# FastDAC.net
KiCad netlist of a schematic drawn in Altium Designer
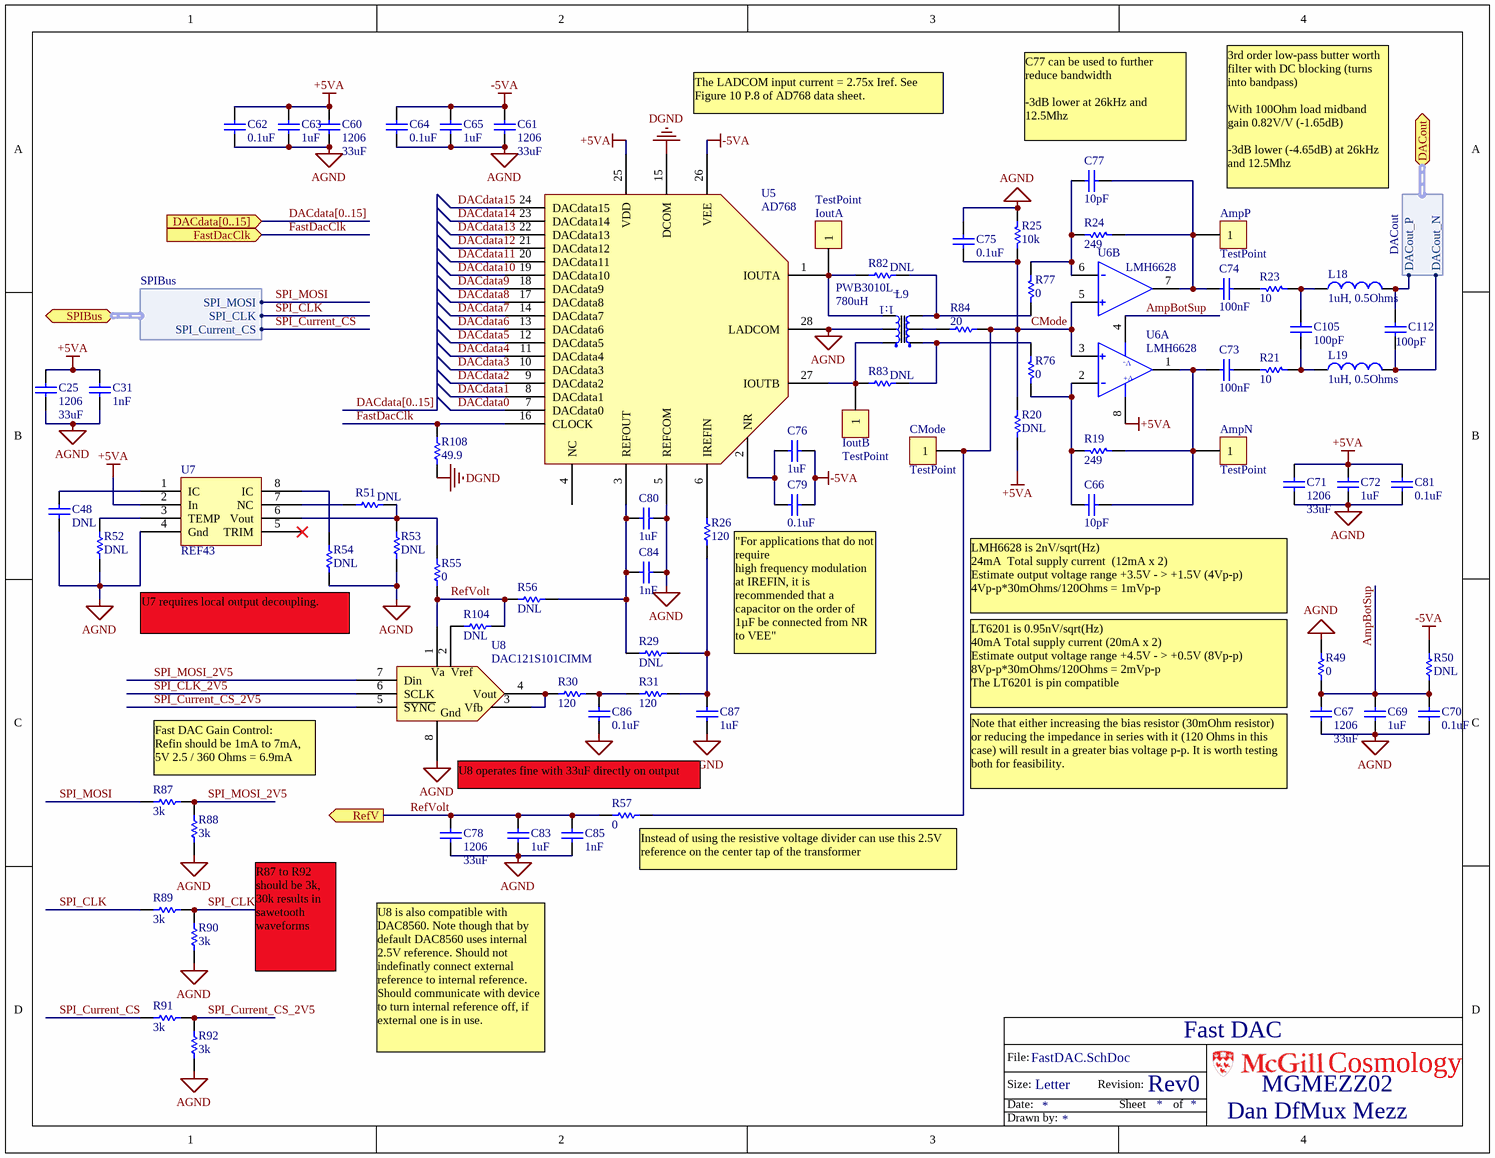
[diagram p0: FastDAC.SchDoc]

(export (version "E")
  (design (tool "Eeschema 10.0.6"))
  (components
    (comp (ref "AmpN")
      (value "TestPoint")
      (footprint "TP-3520-SK")
      (description "TestPoint1")
      (libsource (lib "") (part "TestPoint_3"))
    )
    (comp (ref "AmpP")
      (value "TestPoint")
      (footprint "TP-3520-SK")
      (description "TestPoint1")
      (libsource (lib "") (part "TestPoint_3"))
    )
    (comp (ref "C25")
      (value "33uF")
      (footprint "1206")
      (description "Capacitor, Ceramic, 1210")
      (fields
        (field (name "MANUFACTURER") "TDK Corporation")
        (field (name "MANUFACTURERS PART NUMBER") "C3216X5R1E336M")
      )
      (libsource (lib "MGMEZZ04") (part "CAP 1210"))
    )
    (comp (ref "C31")
      (value "1nF")
      (footprint "0603")
      (description "Capacitor, Ceramic, 0603")
      (fields (field (name "MANUFACTURER") "Generic"))
      (libsource (lib "MGMEZZ04") (part "CAP 0603"))
    )
    (comp (ref "C48")
      (value "DNL")
      (footprint "0603")
      (description "Capacitor, Ceramic, 0603")
      (fields (field (name "MANUFACTURER") "Generic"))
      (libsource (lib "MGMEZZ04") (part "CAP 0603"))
    )
    (comp (ref "C60")
      (value "33uF")
      (footprint "1206")
      (description "Capacitor, Ceramic, 1210")
      (fields
        (field (name "MANUFACTURER") "TDK Corporation")
        (field (name "MANUFACTURERS PART NUMBER") "C3216X5R1E336M")
      )
      (libsource (lib "MGMEZZ04") (part "CAP 1210"))
    )
    (comp (ref "C61")
      (value "33uF")
      (footprint "1206")
      (description "Capacitor, Ceramic, 1210")
      (fields
        (field (name "MANUFACTURER") "TDK Corporation")
        (field (name "MANUFACTURERS PART NUMBER") "C3216X5R1E336M")
      )
      (libsource (lib "MGMEZZ04") (part "CAP 1210"))
    )
    (comp (ref "C62")
      (value "0.1uF")
      (footprint "0603")
      (description "Capacitor, Ceramic, 0603")
      (fields (field (name "MANUFACTURER") "Generic"))
      (libsource (lib "MGMEZZ04") (part "CAP 0603"))
    )
    (comp (ref "C63")
      (value "1uF")
      (footprint "0603")
      (description "Capacitor, Ceramic, 0603")
      (fields
        (field (name "MANUFACTURER") "Generic")
        (field (name "MANUFACTURERS PART NUMBER") "e.g C1608X7R1C105K")
      )
      (libsource (lib "MGMEZZ04") (part "CAP 0603"))
    )
    (comp (ref "C64")
      (value "0.1uF")
      (footprint "0603")
      (description "Capacitor, Ceramic, 0603")
      (fields (field (name "MANUFACTURER") "Generic"))
      (libsource (lib "MGMEZZ04") (part "CAP 0603"))
    )
    (comp (ref "C65")
      (value "1uF")
      (footprint "0603")
      (description "Capacitor, Ceramic, 0603")
      (fields
        (field (name "MANUFACTURER") "Generic")
        (field (name "MANUFACTURERS PART NUMBER") "e.g C1608X7R1C105K")
      )
      (libsource (lib "MGMEZZ04") (part "CAP 0603"))
    )
    (comp (ref "C66")
      (value "10pF")
      (footprint "0603")
      (description "Capacitor, Ceramic, 0603")
      (fields (field (name "MANUFACTURER") "Generic"))
      (libsource (lib "MGMEZZ04") (part "CAP 0603"))
    )
    (comp (ref "C67")
      (value "33uF")
      (footprint "1206")
      (description "Capacitor, Ceramic, 1210")
      (fields
        (field (name "MANUFACTURER") "TDK Corporation")
        (field (name "MANUFACTURERS PART NUMBER") "C3216X5R1E336M")
      )
      (libsource (lib "MGMEZZ04") (part "CAP 1210"))
    )
    (comp (ref "C69")
      (value "1uF")
      (footprint "0603")
      (description "Capacitor, Ceramic, 0603")
      (fields
        (field (name "MANUFACTURER") "Generic")
        (field (name "MANUFACTURERS PART NUMBER") "e.g C1608X7R1C105K")
      )
      (libsource (lib "MGMEZZ04") (part "CAP 0603"))
    )
    (comp (ref "C70")
      (value "0.1uF")
      (footprint "0603")
      (description "Capacitor, Ceramic, 0603")
      (fields (field (name "MANUFACTURER") "Generic"))
      (libsource (lib "MGMEZZ04") (part "CAP 0603"))
    )
    (comp (ref "C71")
      (value "33uF")
      (footprint "1206")
      (description "Capacitor, Ceramic, 1210")
      (fields
        (field (name "MANUFACTURER") "TDK Corporation")
        (field (name "MANUFACTURERS PART NUMBER") "C3216X5R1E336M")
      )
      (libsource (lib "MGMEZZ04") (part "CAP 1210"))
    )
    (comp (ref "C72")
      (value "1uF")
      (footprint "0603")
      (description "Capacitor, Ceramic, 0603")
      (fields
        (field (name "MANUFACTURER") "Generic")
        (field (name "MANUFACTURERS PART NUMBER") "e.g C1608X7R1C105K")
      )
      (libsource (lib "MGMEZZ04") (part "CAP 0603"))
    )
    (comp (ref "C73")
      (value "100nF")
      (footprint "0603")
      (description "Capacitor, Ceramic, 0603")
      (fields (field (name "MANUFACTURER") "Generic"))
      (libsource (lib "MGMEZZ04") (part "CAP 0603"))
    )
    (comp (ref "C74")
      (value "100nF")
      (footprint "0603")
      (description "Capacitor, Ceramic, 0603")
      (fields (field (name "MANUFACTURER") "Generic"))
      (libsource (lib "MGMEZZ04") (part "CAP 0603"))
    )
    (comp (ref "C75")
      (value "0.1uF")
      (footprint "0603")
      (description "Capacitor, Ceramic, 0603")
      (fields (field (name "MANUFACTURER") "Generic"))
      (libsource (lib "MGMEZZ04") (part "CAP 0603"))
    )
    (comp (ref "C76")
      (value "1uF")
      (footprint "0603")
      (description "Capacitor, Ceramic, 0603")
      (fields
        (field (name "MANUFACTURER") "Generic")
        (field (name "MANUFACTURERS PART NUMBER") "e.g C1608X7R1C105K")
      )
      (libsource (lib "MGMEZZ04") (part "CAP 0603"))
    )
    (comp (ref "C77")
      (value "10pF")
      (footprint "0603")
      (description "Capacitor, Ceramic, 0603")
      (fields (field (name "MANUFACTURER") "Generic"))
      (libsource (lib "MGMEZZ04") (part "CAP 0603"))
    )
    (comp (ref "C78")
      (value "33uF")
      (footprint "1206")
      (description "Capacitor, Ceramic, 1210")
      (fields
        (field (name "MANUFACTURER") "TDK Corporation")
        (field (name "MANUFACTURERS PART NUMBER") "C3216X5R1E336M")
      )
      (libsource (lib "MGMEZZ04") (part "CAP 1210"))
    )
    (comp (ref "C79")
      (value "0.1uF")
      (footprint "0603")
      (description "Capacitor, Ceramic, 0603")
      (fields (field (name "MANUFACTURER") "Generic"))
      (libsource (lib "MGMEZZ04") (part "CAP 0603"))
    )
    (comp (ref "C80")
      (value "1uF")
      (footprint "0603")
      (description "Capacitor, Ceramic, 0603")
      (fields
        (field (name "MANUFACTURER") "Generic")
        (field (name "MANUFACTURERS PART NUMBER") "e.g C1608X7R1C105K")
      )
      (libsource (lib "MGMEZZ04") (part "CAP 0603"))
    )
    (comp (ref "C81")
      (value "0.1uF")
      (footprint "0603")
      (description "Capacitor, Ceramic, 0603")
      (fields (field (name "MANUFACTURER") "Generic"))
      (libsource (lib "MGMEZZ04") (part "CAP 0603"))
    )
    (comp (ref "C83")
      (value "1uF")
      (footprint "0603")
      (description "Capacitor, Ceramic, 0603")
      (fields
        (field (name "MANUFACTURER") "Generic")
        (field (name "MANUFACTURERS PART NUMBER") "e.g C1608X7R1C105K")
      )
      (libsource (lib "MGMEZZ04") (part "CAP 0603"))
    )
    (comp (ref "C84")
      (value "1nF")
      (footprint "0603")
      (description "Capacitor, Ceramic, 0603")
      (fields (field (name "MANUFACTURER") "Generic"))
      (libsource (lib "MGMEZZ04") (part "CAP 0603"))
    )
    (comp (ref "C85")
      (value "1nF")
      (footprint "0603")
      (description "Capacitor, Ceramic, 0603")
      (fields (field (name "MANUFACTURER") "Generic"))
      (libsource (lib "MGMEZZ04") (part "CAP 0603"))
    )
    (comp (ref "C86")
      (value "0.1uF")
      (footprint "0603")
      (description "Capacitor, Ceramic, 0603")
      (fields (field (name "MANUFACTURER") "Generic"))
      (libsource (lib "MGMEZZ04") (part "CAP 0603"))
    )
    (comp (ref "C87")
      (value "1uF")
      (footprint "0603")
      (description "Capacitor, Ceramic, 0603")
      (fields
        (field (name "MANUFACTURER") "Generic")
        (field (name "MANUFACTURERS PART NUMBER") "e.g C1608X7R1C105K")
      )
      (libsource (lib "MGMEZZ04") (part "CAP 0603"))
    )
    (comp (ref "C105")
      (value "100pF")
      (footprint "0603")
      (description "Capacitor, Ceramic, 0603")
      (fields (field (name "MANUFACTURER") "Generic"))
      (libsource (lib "MGMEZZ04") (part "CAP 0603"))
    )
    (comp (ref "C112")
      (value "100pF")
      (footprint "0603")
      (description "Capacitor, Ceramic, 0603")
      (fields (field (name "MANUFACTURER") "Generic"))
      (libsource (lib "MGMEZZ04") (part "CAP 0603"))
    )
    (comp (ref "CMode")
      (value "TestPoint")
      (footprint "TP-3520-SK")
      (description "TestPoint1")
      (libsource (lib "MGMEZZ04") (part "TestPoint"))
    )
    (comp (ref "IoutA")
      (value "TestPoint")
      (footprint "TP-3520-SK")
      (description "TestPoint1")
      (libsource (lib "") (part "TestPoint_1"))
    )
    (comp (ref "IoutB")
      (value "TestPoint")
      (footprint "TP-3520-SK")
      (description "TestPoint1")
      (libsource (lib "") (part "TestPoint_2"))
    )
    (comp (ref "L9")
      (value "PWB3010L_")
      (footprint "PWB")
      (description "Transformer")
      (fields (field (name "MANUFACTURER") "Coil Craft") (field (name "ALTIUM_VALUE") "780uH"))
      (libsource (lib "MGMEZZ04") (part "PWB-1-CLB"))
    )
    (comp (ref "L18")
      (value "1uH, 0.5Ohms")
      (footprint "0805")
      (description "Inductor 0805")
      (fields
        (field (name "MANUFACTURER") "EPCOS Inc")
        (field (name "MANUFACTURERS PART NUMBER") "B82498F1102J")
      )
      (libsource (lib "MGMEZZ04") (part "IND 0805"))
    )
    (comp (ref "L19")
      (value "1uH, 0.5Ohms")
      (footprint "0805")
      (description "Inductor 0805")
      (fields
        (field (name "MANUFACTURER") "EPCOS Inc")
        (field (name "MANUFACTURERS PART NUMBER") "B82498F1102J")
      )
      (libsource (lib "MGMEZZ04") (part "IND 0805"))
    )
    (comp (ref "R19")
      (value "249")
      (footprint "0603")
      (description "Resistor")
      (fields (field (name "MANUFACTURER") "Generic"))
      (libsource (lib "MGMEZZ04") (part "RES 0603"))
    )
    (comp (ref "R20")
      (value "DNL")
      (footprint "0603")
      (description "Resistor")
      (fields (field (name "MANUFACTURER") "Generic"))
      (libsource (lib "MGMEZZ04") (part "RES 0603"))
    )
    (comp (ref "R21")
      (value "10")
      (footprint "0603")
      (description "Resistor")
      (fields (field (name "MANUFACTURER") "Generic"))
      (libsource (lib "MGMEZZ04") (part "RES 0603"))
    )
    (comp (ref "R23")
      (value "10")
      (footprint "0603")
      (description "Resistor")
      (fields (field (name "MANUFACTURER") "Generic"))
      (libsource (lib "MGMEZZ04") (part "RES 0603"))
    )
    (comp (ref "R24")
      (value "249")
      (footprint "0603")
      (description "Resistor")
      (fields (field (name "MANUFACTURER") "Generic"))
      (libsource (lib "MGMEZZ04") (part "RES 0603"))
    )
    (comp (ref "R25")
      (value "10k")
      (footprint "0603")
      (description "Resistor")
      (fields (field (name "MANUFACTURER") "Generic"))
      (libsource (lib "MGMEZZ04") (part "RES 0603"))
    )
    (comp (ref "R26")
      (value "120")
      (footprint "0603")
      (description "Resistor")
      (fields (field (name "MANUFACTURER") "Generic"))
      (libsource (lib "MGMEZZ04") (part "RES 0603"))
    )
    (comp (ref "R29")
      (value "DNL")
      (footprint "0603")
      (description "Resistor")
      (fields (field (name "MANUFACTURER") "Generic"))
      (libsource (lib "MGMEZZ04") (part "RES 0603"))
    )
    (comp (ref "R30")
      (value "120")
      (footprint "0603")
      (description "Resistor")
      (fields (field (name "MANUFACTURER") "Generic"))
      (libsource (lib "MGMEZZ04") (part "RES 0603"))
    )
    (comp (ref "R31")
      (value "120")
      (footprint "0603")
      (description "Resistor")
      (fields (field (name "MANUFACTURER") "Generic"))
      (libsource (lib "MGMEZZ04") (part "RES 0603"))
    )
    (comp (ref "R49")
      (value "0")
      (footprint "0603")
      (description "Resistor")
      (fields (field (name "MANUFACTURER") "Generic"))
      (libsource (lib "MGMEZZ04") (part "RES 0603"))
    )
    (comp (ref "R50")
      (value "DNL")
      (footprint "0603")
      (description "Resistor")
      (fields (field (name "MANUFACTURER") "Generic"))
      (libsource (lib "MGMEZZ04") (part "RES 0603"))
    )
    (comp (ref "R51")
      (value "DNL")
      (footprint "0603")
      (description "Resistor")
      (fields (field (name "MANUFACTURER") "Generic"))
      (libsource (lib "MGMEZZ04") (part "RES 0603"))
    )
    (comp (ref "R52")
      (value "DNL")
      (footprint "0603")
      (description "Resistor")
      (fields (field (name "MANUFACTURER") "Generic"))
      (libsource (lib "MGMEZZ04") (part "RES 0603"))
    )
    (comp (ref "R53")
      (value "DNL")
      (footprint "0603")
      (description "Resistor")
      (fields (field (name "MANUFACTURER") "Generic"))
      (libsource (lib "MGMEZZ04") (part "RES 0603"))
    )
    (comp (ref "R54")
      (value "DNL")
      (footprint "0603")
      (description "Resistor")
      (fields (field (name "MANUFACTURER") "Generic"))
      (libsource (lib "MGMEZZ04") (part "RES 0603"))
    )
    (comp (ref "R55")
      (value "0")
      (footprint "0603")
      (description "Resistor")
      (fields (field (name "MANUFACTURER") "Generic"))
      (libsource (lib "MGMEZZ04") (part "RES 0603"))
    )
    (comp (ref "R56")
      (value "DNL")
      (footprint "0603")
      (description "Resistor")
      (fields (field (name "MANUFACTURER") "Generic"))
      (libsource (lib "MGMEZZ04") (part "RES 0603"))
    )
    (comp (ref "R57")
      (value "0")
      (footprint "0603")
      (description "Resistor")
      (fields (field (name "MANUFACTURER") "Generic"))
      (libsource (lib "MGMEZZ04") (part "RES 0603"))
    )
    (comp (ref "R76")
      (value "0")
      (footprint "0603")
      (description "Resistor")
      (fields (field (name "MANUFACTURER") "Generic"))
      (libsource (lib "MGMEZZ04") (part "RES 0603"))
    )
    (comp (ref "R77")
      (value "0")
      (footprint "0603")
      (description "Resistor")
      (fields (field (name "MANUFACTURER") "Generic"))
      (libsource (lib "MGMEZZ04") (part "RES 0603"))
    )
    (comp (ref "R82")
      (value "DNL")
      (footprint "0603")
      (description "Resistor")
      (fields (field (name "MANUFACTURER") "Generic"))
      (libsource (lib "MGMEZZ04") (part "RES 0603"))
    )
    (comp (ref "R83")
      (value "DNL")
      (footprint "0603")
      (description "Resistor")
      (fields (field (name "MANUFACTURER") "Generic"))
      (libsource (lib "MGMEZZ04") (part "RES 0603"))
    )
    (comp (ref "R84")
      (value "20")
      (footprint "0603")
      (description "Resistor")
      (fields (field (name "MANUFACTURER") "Generic"))
      (libsource (lib "MGMEZZ04") (part "RES 0603"))
    )
    (comp (ref "R87")
      (value "3k")
      (footprint "0603")
      (description "Resistor")
      (fields (field (name "MANUFACTURER") "Generic"))
      (libsource (lib "MGMEZZ04") (part "RES 0603"))
    )
    (comp (ref "R88")
      (value "3k")
      (footprint "0603")
      (description "Resistor")
      (fields (field (name "MANUFACTURER") "Generic"))
      (libsource (lib "MGMEZZ04") (part "RES 0603"))
    )
    (comp (ref "R89")
      (value "3k")
      (footprint "0603")
      (description "Resistor")
      (fields (field (name "MANUFACTURER") "Generic"))
      (libsource (lib "MGMEZZ04") (part "RES 0603"))
    )
    (comp (ref "R90")
      (value "3k")
      (footprint "0603")
      (description "Resistor")
      (fields (field (name "MANUFACTURER") "Generic"))
      (libsource (lib "MGMEZZ04") (part "RES 0603"))
    )
    (comp (ref "R91")
      (value "3k")
      (footprint "0603")
      (description "Resistor")
      (fields (field (name "MANUFACTURER") "Generic"))
      (libsource (lib "MGMEZZ04") (part "RES 0603"))
    )
    (comp (ref "R92")
      (value "3k")
      (footprint "0603")
      (description "Resistor")
      (fields (field (name "MANUFACTURER") "Generic"))
      (libsource (lib "MGMEZZ04") (part "RES 0603"))
    )
    (comp (ref "R104")
      (value "DNL")
      (footprint "0603")
      (description "Resistor")
      (fields (field (name "MANUFACTURER") "Generic"))
      (libsource (lib "MGMEZZ04") (part "RES 0603"))
    )
    (comp (ref "R108")
      (value "49.9")
      (footprint "0603")
      (description "Resistor")
      (fields (field (name "MANUFACTURER") "Generic"))
      (libsource (lib "MGMEZZ04") (part "RES 0603"))
    )
    (comp (ref "U5")
      (value "AD768")
      (footprint "SOIC 28 300mils")
      (description "DAC 16bit 30MSPS")
      (fields
        (field (name "MANUFACTURERS PART NUMBER") "AD768ARZ")
        (field (name "MANUFACTURER") "Analog Devices")
      )
      (libsource (lib "MGMEZZ04") (part "AD768"))
    )
    (comp (ref "U6")
      (value "LMH6628")
      (footprint "SO8")
      (description "Dual Opamp 200Mhz GBP Soic 8")
      (fields
        (field (name "MANUFACTURERS PART NUMBER") "LMH6628MA/NOPB")
        (field (name "MANUFACTURER") "National Semiconductor")
      )
      (libsource (lib "MGMEZZ04") (part "LMH6628"))
    )
    (comp (ref "U7")
      (value "REF43")
      (footprint "SO8")
      (description "Voltage Referance")
      (fields
        (field (name "MANUFACTURER") "Analog Devices")
        (field (name "MANUFACTURERS PART NUMBER") "REF43GSZ")
      )
      (libsource (lib "MGMEZZ04") (part "REF43"))
    )
    (comp (ref "U8")
      (value "DAC121S101CIMM")
      (footprint "MSOP-8")
      (description "CONV D/A 12BIT MICROPWR 8MSOP")
      (fields
        (field (name "MANUFACTURER") "National Semiconductor")
        (field (name "MANUFACTURERS PART NUMBER") "DAC121S101CIMM/NOPB")
      )
      (libsource (lib "MGMEZZ04") (part "DAC121S101CIMM/NOPB"))
    )
  )
  (nets
    (net (code "3") (name "+5VA") (class "Default")
      (node (ref "C25") (pin "1") (pinfunction "1_1") (pintype "passive"))
      (node (ref "C31") (pin "1") (pinfunction "1_1") (pintype "passive"))
      (node (ref "C60") (pin "2") (pinfunction "2_2") (pintype "passive"))
      (node (ref "C62") (pin "2") (pinfunction "2_2") (pintype "passive"))
      (node (ref "C63") (pin "2") (pinfunction "2_2") (pintype "passive"))
      (node (ref "C71") (pin "2") (pinfunction "2_2") (pintype "passive"))
      (node (ref "C72") (pin "1") (pinfunction "1_1") (pintype "passive"))
      (node (ref "C81") (pin "1") (pinfunction "1_1") (pintype "passive"))
      (node (ref "R20") (pin "2") (pinfunction "2_2") (pintype "passive"))
      (node (ref "U5") (pin "25") (pinfunction "VDD_25") (pintype "passive"))
      (node (ref "U6") (pin "8") (pinfunction "V+_8") (pintype "power_in"))
      (node (ref "U7") (pin "2") (pinfunction "In_2") (pintype "passive"))
    )
    (net (code "4") (name "-5VA") (class "Default")
      (node (ref "C61") (pin "2") (pinfunction "2_2") (pintype "passive"))
      (node (ref "C64") (pin "2") (pinfunction "2_2") (pintype "passive"))
      (node (ref "C65") (pin "2") (pinfunction "2_2") (pintype "passive"))
      (node (ref "C76") (pin "1") (pinfunction "1_1") (pintype "passive"))
      (node (ref "C79") (pin "1") (pinfunction "1_1") (pintype "passive"))
      (node (ref "R50") (pin "2") (pinfunction "2_2") (pintype "passive"))
      (node (ref "U5") (pin "26") (pinfunction "VEE_26") (pintype "passive"))
    )
    (net (code "5") (name "/AmpBotSup") (class "Default")
      (node (ref "C67") (pin "2") (pinfunction "2_2") (pintype "passive"))
      (node (ref "C69") (pin "1") (pinfunction "1_1") (pintype "passive"))
      (node (ref "C70") (pin "1") (pinfunction "1_1") (pintype "passive"))
      (node (ref "R49") (pin "1") (pinfunction "1_1") (pintype "passive"))
      (node (ref "R50") (pin "1") (pinfunction "1_1") (pintype "passive"))
      (node (ref "U6") (pin "4") (pinfunction "V-_4") (pintype "power_in"))
    )
    (net (code "6") (name "/CMode") (class "Default")
      (node (ref "C75") (pin "2") (pinfunction "2_2") (pintype "passive"))
      (node (ref "CMode") (pin "1") (pinfunction "1_1") (pintype "passive"))
      (node (ref "R20") (pin "1") (pinfunction "1_1") (pintype "passive"))
      (node (ref "R25") (pin "2") (pinfunction "2_2") (pintype "passive"))
      (node (ref "R57") (pin "2") (pinfunction "2_2") (pintype "passive"))
      (node (ref "R84") (pin "2") (pinfunction "2_2") (pintype "passive"))
      (node (ref "U6") (pin "3") (pinfunction "IN+_3") (pintype "passive"))
      (node (ref "U6") (pin "5") (pinfunction "IN+_5") (pintype "passive"))
    )
    (net (code "7") (name "/DACdata0") (class "Default")
      (node (ref "U5") (pin "7") (pinfunction "DACdata0_7") (pintype "passive"))
    )
    (net (code "8") (name "/DACdata1") (class "Default")
      (node (ref "U5") (pin "8") (pinfunction "DACdata1_8") (pintype "passive"))
    )
    (net (code "9") (name "/DACdata2") (class "Default")
      (node (ref "U5") (pin "9") (pinfunction "DACdata2_9") (pintype "passive"))
    )
    (net (code "10") (name "/DACdata3") (class "Default")
      (node (ref "U5") (pin "10") (pinfunction "DACdata3_10") (pintype "passive"))
    )
    (net (code "11") (name "/DACdata4") (class "Default")
      (node (ref "U5") (pin "11") (pinfunction "DACdata4_11") (pintype "passive"))
    )
    (net (code "12") (name "/DACdata5") (class "Default")
      (node (ref "U5") (pin "12") (pinfunction "DACdata5_12") (pintype "passive"))
    )
    (net (code "13") (name "/DACdata6") (class "Default")
      (node (ref "U5") (pin "13") (pinfunction "DACdata6_13") (pintype "passive"))
    )
    (net (code "14") (name "/DACdata7") (class "Default")
      (node (ref "U5") (pin "14") (pinfunction "DACdata7_14") (pintype "passive"))
    )
    (net (code "15") (name "/DACdata8") (class "Default")
      (node (ref "U5") (pin "17") (pinfunction "DACdata8_17") (pintype "passive"))
    )
    (net (code "16") (name "/DACdata9") (class "Default")
      (node (ref "U5") (pin "18") (pinfunction "DACdata9_18") (pintype "passive"))
    )
    (net (code "17") (name "/DACdata10") (class "Default")
      (node (ref "U5") (pin "19") (pinfunction "DACdata10_19") (pintype "passive"))
    )
    (net (code "18") (name "/DACdata11") (class "Default")
      (node (ref "U5") (pin "20") (pinfunction "DACdata11_20") (pintype "passive"))
    )
    (net (code "19") (name "/DACdata12") (class "Default")
      (node (ref "U5") (pin "21") (pinfunction "DACdata12_21") (pintype "passive"))
    )
    (net (code "20") (name "/DACdata13") (class "Default")
      (node (ref "U5") (pin "22") (pinfunction "DACdata13_22") (pintype "passive"))
    )
    (net (code "21") (name "/DACdata14") (class "Default")
      (node (ref "U5") (pin "23") (pinfunction "DACdata14_23") (pintype "passive"))
    )
    (net (code "22") (name "/DACdata15") (class "Default")
      (node (ref "U5") (pin "24") (pinfunction "DACdata15_24") (pintype "passive"))
    )
    (net (code "24") (name "/FastDacClk") (class "Default")
      (node (ref "R108") (pin "2") (pinfunction "2_2") (pintype "passive"))
      (node (ref "U5") (pin "16") (pinfunction "CLOCK_16") (pintype "passive"))
    )
    (net (code "25") (name "/RefVolt") (class "Default")
      (node (ref "C78") (pin "1") (pinfunction "1_1") (pintype "passive"))
      (node (ref "C83") (pin "1") (pinfunction "1_1") (pintype "passive"))
      (node (ref "C85") (pin "1") (pinfunction "1_1") (pintype "passive"))
      (node (ref "R104") (pin "2") (pinfunction "2_2") (pintype "passive"))
      (node (ref "R55") (pin "2") (pinfunction "2_2") (pintype "passive"))
      (node (ref "R56") (pin "1") (pinfunction "1_1") (pintype "passive"))
      (node (ref "R57") (pin "1") (pinfunction "1_1") (pintype "passive"))
      (node (ref "U8") (pin "1") (pinfunction "Va_1") (pintype "passive"))
    )
    (net (code "26") (name "/SPI_CLK") (class "Default")
      (node (ref "R89") (pin "1") (pinfunction "1_1") (pintype "passive"))
    )
    (net (code "27") (name "/SPI_CLK_2V5") (class "Default")
      (node (ref "R89") (pin "2") (pinfunction "2_2") (pintype "passive"))
      (node (ref "R90") (pin "1") (pinfunction "1_1") (pintype "passive"))
      (node (ref "U8") (pin "6") (pinfunction "SCLK_6") (pintype "passive"))
    )
    (net (code "28") (name "/SPI_Current_CS") (class "Default")
      (node (ref "R91") (pin "1") (pinfunction "1_1") (pintype "passive"))
    )
    (net (code "29") (name "/SPI_Current_CS_2V5") (class "Default")
      (node (ref "R91") (pin "2") (pinfunction "2_2") (pintype "passive"))
      (node (ref "R92") (pin "1") (pinfunction "1_1") (pintype "passive"))
      (node (ref "U8") (pin "5") (pinfunction "~{SYNC}_5") (pintype "passive"))
    )
    (net (code "30") (name "/SPI_MOSI") (class "Default")
      (node (ref "R87") (pin "1") (pinfunction "1_1") (pintype "passive"))
    )
    (net (code "31") (name "/SPI_MOSI_2V5") (class "Default")
      (node (ref "R87") (pin "2") (pinfunction "2_2") (pintype "passive"))
      (node (ref "R88") (pin "1") (pinfunction "1_1") (pintype "passive"))
      (node (ref "U8") (pin "7") (pinfunction "Din_7") (pintype "passive"))
    )
    (net (code "34") (name "AGND") (class "Default")
      (node (ref "C25") (pin "2") (pinfunction "2_2") (pintype "passive"))
      (node (ref "C31") (pin "2") (pinfunction "2_2") (pintype "passive"))
      (node (ref "C48") (pin "2") (pinfunction "2_2") (pintype "passive"))
      (node (ref "C60") (pin "1") (pinfunction "1_1") (pintype "passive"))
      (node (ref "C61") (pin "1") (pinfunction "1_1") (pintype "passive"))
      (node (ref "C62") (pin "1") (pinfunction "1_1") (pintype "passive"))
      (node (ref "C63") (pin "1") (pinfunction "1_1") (pintype "passive"))
      (node (ref "C64") (pin "1") (pinfunction "1_1") (pintype "passive"))
      (node (ref "C65") (pin "1") (pinfunction "1_1") (pintype "passive"))
      (node (ref "C67") (pin "1") (pinfunction "1_1") (pintype "passive"))
      (node (ref "C69") (pin "2") (pinfunction "2_2") (pintype "passive"))
      (node (ref "C70") (pin "2") (pinfunction "2_2") (pintype "passive"))
      (node (ref "C71") (pin "1") (pinfunction "1_1") (pintype "passive"))
      (node (ref "C72") (pin "2") (pinfunction "2_2") (pintype "passive"))
      (node (ref "C75") (pin "1") (pinfunction "1_1") (pintype "passive"))
      (node (ref "C78") (pin "2") (pinfunction "2_2") (pintype "passive"))
      (node (ref "C80") (pin "2") (pinfunction "2_2") (pintype "passive"))
      (node (ref "C81") (pin "2") (pinfunction "2_2") (pintype "passive"))
      (node (ref "C83") (pin "2") (pinfunction "2_2") (pintype "passive"))
      (node (ref "C84") (pin "2") (pinfunction "2_2") (pintype "passive"))
      (node (ref "C85") (pin "2") (pinfunction "2_2") (pintype "passive"))
      (node (ref "C86") (pin "2") (pinfunction "2_2") (pintype "passive"))
      (node (ref "C87") (pin "2") (pinfunction "2_2") (pintype "passive"))
      (node (ref "L9") (pin "2") (pinfunction "PrimCent_2") (pintype "passive"))
      (node (ref "R25") (pin "1") (pinfunction "1_1") (pintype "passive"))
      (node (ref "R49") (pin "2") (pinfunction "2_2") (pintype "passive"))
      (node (ref "R52") (pin "2") (pinfunction "2_2") (pintype "passive"))
      (node (ref "R53") (pin "1") (pinfunction "1_1") (pintype "passive"))
      (node (ref "R54") (pin "2") (pinfunction "2_2") (pintype "passive"))
      (node (ref "R88") (pin "2") (pinfunction "2_2") (pintype "passive"))
      (node (ref "R90") (pin "2") (pinfunction "2_2") (pintype "passive"))
      (node (ref "R92") (pin "2") (pinfunction "2_2") (pintype "passive"))
      (node (ref "U5") (pin "28") (pinfunction "LADCOM_28") (pintype "passive"))
      (node (ref "U5") (pin "5") (pinfunction "REFCOM_5") (pintype "passive"))
      (node (ref "U7") (pin "4") (pinfunction "Gnd_4") (pintype "passive"))
      (node (ref "U8") (pin "8") (pinfunction "Gnd_8") (pintype "passive"))
    )
    (net (code "35") (name "DGND") (class "Default")
      (node (ref "R108") (pin "1") (pinfunction "1_1") (pintype "passive"))
      (node (ref "U5") (pin "15") (pinfunction "DCOM_15") (pintype "passive"))
    )
    (net (code "36") (name "Net-(C48-Pad1)") (class "Default")
      (node (ref "C48") (pin "1") (pinfunction "1_1") (pintype "passive"))
      (node (ref "U7") (pin "1") (pinfunction "IC_1") (pintype "passive"))
    )
    (net (code "37") (name "Net-(C73-Pad1)") (class "Default")
      (node (ref "C73") (pin "1") (pinfunction "1_1") (pintype "passive"))
      (node (ref "R21") (pin "1") (pinfunction "1_1") (pintype "passive"))
    )
    (net (code "38") (name "Net-(C74-Pad1)") (class "Default")
      (node (ref "C74") (pin "1") (pinfunction "1_1") (pintype "passive"))
      (node (ref "R23") (pin "1") (pinfunction "1_1") (pintype "passive"))
    )
    (net (code "39") (name "Net-(C86-Pad1)") (class "Default")
      (node (ref "C86") (pin "1") (pinfunction "1_1") (pintype "passive"))
      (node (ref "R30") (pin "1") (pinfunction "1_1") (pintype "passive"))
      (node (ref "R31") (pin "2") (pinfunction "2_2") (pintype "passive"))
    )
    (net (code "40") (name "Net-(C87-Pad1)") (class "Default")
      (node (ref "C87") (pin "1") (pinfunction "1_1") (pintype "passive"))
      (node (ref "R26") (pin "2") (pinfunction "2_2") (pintype "passive"))
      (node (ref "R29") (pin "2") (pinfunction "2_2") (pintype "passive"))
      (node (ref "R31") (pin "1") (pinfunction "1_1") (pintype "passive"))
    )
    (net (code "41") (name "Net-(C105-Pad1)") (class "Default")
      (node (ref "C105") (pin "1") (pinfunction "1_1") (pintype "passive"))
      (node (ref "L18") (pin "1") (pinfunction "1_1") (pintype "passive"))
      (node (ref "R23") (pin "2") (pinfunction "2_2") (pintype "passive"))
    )
    (net (code "42") (name "Net-(C105-Pad2)") (class "Default")
      (node (ref "C105") (pin "2") (pinfunction "2_2") (pintype "passive"))
      (node (ref "L19") (pin "1") (pinfunction "1_1") (pintype "passive"))
      (node (ref "R21") (pin "2") (pinfunction "2_2") (pintype "passive"))
    )
    (net (code "43") (name "Net-(C112-Pad1)") (class "Default")
      (node (ref "C112") (pin "1") (pinfunction "1_1") (pintype "passive"))
      (node (ref "L18") (pin "2") (pinfunction "2_2") (pintype "passive"))
    )
    (net (code "44") (name "Net-(C112-Pad2)") (class "Default")
      (node (ref "C112") (pin "2") (pinfunction "2_2") (pintype "passive"))
      (node (ref "L19") (pin "2") (pinfunction "2_2") (pintype "passive"))
    )
    (net (code "45") (name "Net-(L9-Prim)") (class "Default")
      (node (ref "IoutA") (pin "1") (pinfunction "1_1") (pintype "passive"))
      (node (ref "L9") (pin "3") (pinfunction "Prim_3") (pintype "passive"))
      (node (ref "R82") (pin "2") (pinfunction "2_2") (pintype "passive"))
      (node (ref "U5") (pin "1") (pinfunction "IOUTA_1") (pintype "passive"))
    )
    (net (code "46") (name "Net-(L9-PrimDot)") (class "Default")
      (node (ref "IoutB") (pin "1") (pinfunction "1_1") (pintype "passive"))
      (node (ref "L9") (pin "1") (pinfunction "PrimDot_1") (pintype "passive"))
      (node (ref "R83") (pin "2") (pinfunction "2_2") (pintype "passive"))
      (node (ref "U5") (pin "27") (pinfunction "IOUTB_27") (pintype "passive"))
    )
    (net (code "47") (name "Net-(L9-Sec)") (class "Default")
      (node (ref "L9") (pin "4") (pinfunction "Sec_4") (pintype "passive"))
      (node (ref "R77") (pin "1") (pinfunction "1_1") (pintype "passive"))
      (node (ref "R82") (pin "1") (pinfunction "1_1") (pintype "passive"))
    )
    (net (code "48") (name "Net-(L9-SecCent)") (class "Default")
      (node (ref "L9") (pin "5") (pinfunction "SecCent_5") (pintype "passive"))
      (node (ref "R84") (pin "1") (pinfunction "1_1") (pintype "passive"))
    )
    (net (code "49") (name "Net-(L9-SecDot)") (class "Default")
      (node (ref "L9") (pin "6") (pinfunction "SecDot_6") (pintype "passive"))
      (node (ref "R76") (pin "2") (pinfunction "2_2") (pintype "passive"))
      (node (ref "R83") (pin "1") (pinfunction "1_1") (pintype "passive"))
    )
    (net (code "50") (name "Net-(R54-Pad1)") (class "Default")
      (node (ref "R54") (pin "1") (pinfunction "1_1") (pintype "passive"))
      (node (ref "U7") (pin "8") (pinfunction "IC_8") (pintype "passive"))
    )
    (net (code "51") (name "Net-(U5-IREFIN)") (class "Default")
      (node (ref "R26") (pin "1") (pinfunction "1_1") (pintype "passive"))
      (node (ref "U5") (pin "6") (pinfunction "IREFIN_6") (pintype "passive"))
    )
    (net (code "52") (name "Net-(U5-NR)") (class "Default")
      (node (ref "C76") (pin "2") (pinfunction "2_2") (pintype "passive"))
      (node (ref "C79") (pin "2") (pinfunction "2_2") (pintype "passive"))
      (node (ref "U5") (pin "2") (pinfunction "NR_2") (pintype "passive"))
    )
    (net (code "53") (name "Net-(U5-REFOUT)") (class "Default")
      (node (ref "C80") (pin "1") (pinfunction "1_1") (pintype "passive"))
      (node (ref "C84") (pin "1") (pinfunction "1_1") (pintype "passive"))
      (node (ref "R29") (pin "1") (pinfunction "1_1") (pintype "passive"))
      (node (ref "R56") (pin "2") (pinfunction "2_2") (pintype "passive"))
      (node (ref "U5") (pin "3") (pinfunction "REFOUT_3") (pintype "passive"))
    )
    (net (code "54") (name "Net-(U6A-IN-)") (class "Default")
      (node (ref "C66") (pin "1") (pinfunction "1_1") (pintype "passive"))
      (node (ref "R19") (pin "1") (pinfunction "1_1") (pintype "passive"))
      (node (ref "R76") (pin "1") (pinfunction "1_1") (pintype "passive"))
      (node (ref "U6") (pin "2") (pinfunction "IN-_2") (pintype "passive"))
    )
    (net (code "55") (name "Net-(U6A-Out)") (class "Default")
      (node (ref "AmpN") (pin "1") (pinfunction "1_1") (pintype "passive"))
      (node (ref "C66") (pin "2") (pinfunction "2_2") (pintype "passive"))
      (node (ref "C73") (pin "2") (pinfunction "2_2") (pintype "passive"))
      (node (ref "R19") (pin "2") (pinfunction "2_2") (pintype "passive"))
      (node (ref "U6") (pin "1") (pinfunction "Out_1") (pintype "passive"))
    )
    (net (code "56") (name "Net-(U6B-IN-)") (class "Default")
      (node (ref "C77") (pin "1") (pinfunction "1_1") (pintype "passive"))
      (node (ref "R24") (pin "1") (pinfunction "1_1") (pintype "passive"))
      (node (ref "R77") (pin "2") (pinfunction "2_2") (pintype "passive"))
      (node (ref "U6") (pin "6") (pinfunction "IN-_6") (pintype "passive"))
    )
    (net (code "57") (name "Net-(U6B-Out)") (class "Default")
      (node (ref "AmpP") (pin "1") (pinfunction "1_1") (pintype "passive"))
      (node (ref "C74") (pin "2") (pinfunction "2_2") (pintype "passive"))
      (node (ref "C77") (pin "2") (pinfunction "2_2") (pintype "passive"))
      (node (ref "R24") (pin "2") (pinfunction "2_2") (pintype "passive"))
      (node (ref "U6") (pin "7") (pinfunction "Out_7") (pintype "passive"))
    )
    (net (code "58") (name "Net-(U7-NC)") (class "Default")
      (node (ref "R51") (pin "2") (pinfunction "2_2") (pintype "passive"))
      (node (ref "U7") (pin "7") (pinfunction "NC_7") (pintype "passive"))
    )
    (net (code "59") (name "Net-(U7-TEMP)") (class "Default")
      (node (ref "R52") (pin "1") (pinfunction "1_1") (pintype "passive"))
      (node (ref "U7") (pin "3") (pinfunction "TEMP_3") (pintype "passive"))
    )
    (net (code "60") (name "Net-(U7-Vout)") (class "Default")
      (node (ref "R51") (pin "1") (pinfunction "1_1") (pintype "passive"))
      (node (ref "R53") (pin "2") (pinfunction "2_2") (pintype "passive"))
      (node (ref "R55") (pin "1") (pinfunction "1_1") (pintype "passive"))
      (node (ref "U7") (pin "6") (pinfunction "Vout_6") (pintype "passive"))
    )
    (net (code "61") (name "Net-(U8-Vfb)") (class "Default")
      (node (ref "R30") (pin "2") (pinfunction "2_2") (pintype "passive"))
      (node (ref "U8") (pin "3") (pinfunction "Vfb_3") (pintype "passive"))
      (node (ref "U8") (pin "4") (pinfunction "Vout_4") (pintype "passive"))
    )
    (net (code "62") (name "Net-(U8-Vref)") (class "Default")
      (node (ref "R104") (pin "1") (pinfunction "1_1") (pintype "passive"))
      (node (ref "U8") (pin "2") (pinfunction "Vref_2") (pintype "passive"))
    )
    (net (code "63") (name "unconnected-(U5-NC-Pad4)") (class "Default")
      (node (ref "U5") (pin "4") (pinfunction "NC_4") (pintype "passive"))
    )
    (net (code "64") (name "unconnected-(U7-TRIM-Pad5)") (class "Default")
      (node (ref "U7") (pin "5") (pinfunction "TRIM_5") (pintype "passive+no_connect"))
    )
    (net (code "65") (name "unconnected-(U8-NC-Pad2)") (class "Default")
      (node (ref "U8") (pin "2") (pinfunction "NC_2") (pintype "passive"))
    )
    (net (code "66") (name "unconnected-(U8-NC-Pad3)") (class "Default")
      (node (ref "U8") (pin "3") (pinfunction "NC_3") (pintype "passive"))
    )
  )
)
